# PD.net
KiCad netlist of a schematic drawn in EAGLE
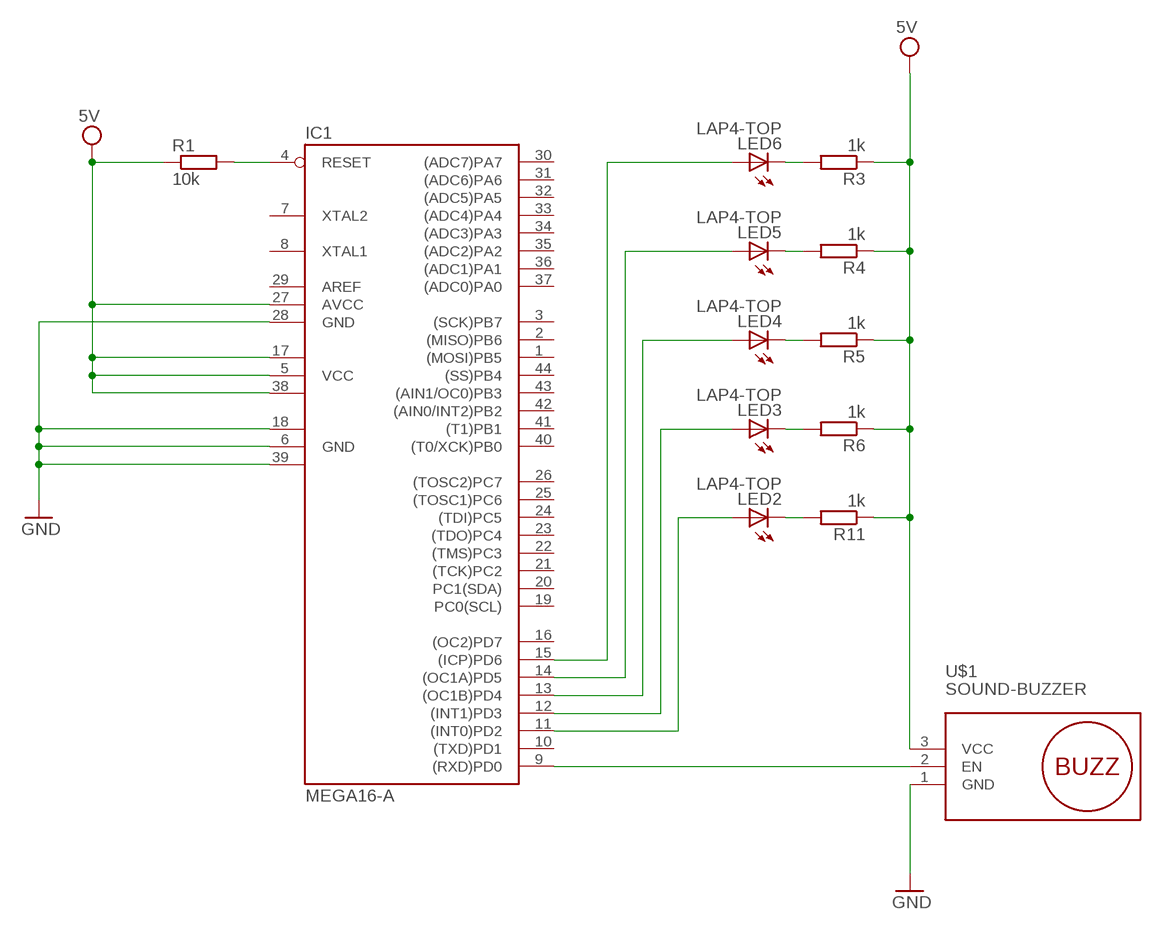
[diagram p0: schematic, sheet 1]

(export (version "E")
  (design (tool "Eeschema 10.0.6"))
  (components
    (comp (ref "IC1")
      (value "MEGA16-A")
      (footprint "eagle-import:TQFP44")
      (fields (field (name "MPN") "ATMEGA16-16AU"))
      (libsource (lib "eagle-import") (part "MEGA16-A"))
    )
    (comp (ref "LED2")
      (value "LAP4-TOP")
      (footprint "eagle-import:P47F-TOP")
      (libsource (lib "eagle-import") (part "P4-TOPLA"))
    )
    (comp (ref "LED3")
      (value "LAP4-TOP")
      (footprint "eagle-import:P47F-TOP")
      (libsource (lib "eagle-import") (part "P4-TOPLA"))
    )
    (comp (ref "LED4")
      (value "LAP4-TOP")
      (footprint "eagle-import:P47F-TOP")
      (libsource (lib "eagle-import") (part "P4-TOPLA"))
    )
    (comp (ref "LED5")
      (value "LAP4-TOP")
      (footprint "eagle-import:P47F-TOP")
      (libsource (lib "eagle-import") (part "P4-TOPLA"))
    )
    (comp (ref "LED6")
      (value "LAP4-TOP")
      (footprint "eagle-import:P47F-TOP")
      (libsource (lib "eagle-import") (part "P4-TOPLA"))
    )
    (comp (ref "R1")
      (value "10k")
      (footprint "eagle-import:M0805")
      (libsource (lib "eagle-import") (part "R-EU_M0805"))
    )
    (comp (ref "R3")
      (value "1k")
      (footprint "eagle-import:M0805")
      (libsource (lib "eagle-import") (part "R-EU_M0805"))
    )
    (comp (ref "R4")
      (value "1k")
      (footprint "eagle-import:M0805")
      (libsource (lib "eagle-import") (part "R-EU_M0805"))
    )
    (comp (ref "R5")
      (value "1k")
      (footprint "eagle-import:M0805")
      (libsource (lib "eagle-import") (part "R-EU_M0805"))
    )
    (comp (ref "R6")
      (value "1k")
      (footprint "eagle-import:M0805")
      (libsource (lib "eagle-import") (part "R-EU_M0805"))
    )
    (comp (ref "R11")
      (value "1k")
      (footprint "eagle-import:M0805")
      (libsource (lib "eagle-import") (part "R-EU_M0805"))
    )
    (comp (ref "U$1")
      (value "SOUND-BUZZER")
      (footprint "eagle-import:SOUND-BUZZER")
      (libsource (lib "eagle-import") (part "SOUND-BUZZER"))
    )
  )
  (nets
    (net (code "1") (name "5V") (class "Default")
      (node (ref "IC1") (pin "17") (pinfunction "VCC1_17") (pintype "power_in"))
      (node (ref "IC1") (pin "27") (pinfunction "AVCC_27") (pintype "power_in"))
      (node (ref "IC1") (pin "38") (pinfunction "VCC2_38") (pintype "power_in"))
      (node (ref "IC1") (pin "5") (pinfunction "VCC_5") (pintype "power_in"))
      (node (ref "R1") (pin "1") (pinfunction "1_1") (pintype "passive"))
      (node (ref "R11") (pin "1") (pinfunction "1_1") (pintype "passive"))
      (node (ref "R3") (pin "1") (pinfunction "1_1") (pintype "passive"))
      (node (ref "R4") (pin "1") (pinfunction "1_1") (pintype "passive"))
      (node (ref "R5") (pin "1") (pinfunction "1_1") (pintype "passive"))
      (node (ref "R6") (pin "1") (pinfunction "1_1") (pintype "passive"))
      (node (ref "U$1") (pin "3") (pinfunction "VCC_3") (pintype "power_in"))
    )
    (net (code "2") (name "GND") (class "Default")
      (node (ref "IC1") (pin "18") (pinfunction "GND1_18") (pintype "power_in"))
      (node (ref "IC1") (pin "28") (pinfunction "GND_28") (pintype "power_in"))
      (node (ref "IC1") (pin "39") (pinfunction "GND2_39") (pintype "power_in"))
      (node (ref "IC1") (pin "6") (pinfunction "GND_6") (pintype "power_in"))
      (node (ref "U$1") (pin "1") (pinfunction "GND_1") (pintype "power_in"))
    )
    (net (code "3") (name "Net-(IC1-(ICP)PD6)") (class "Default")
      (node (ref "IC1") (pin "15") (pinfunction "(ICP)PD6_15") (pintype "bidirectional"))
      (node (ref "LED6") (pin "A") (pinfunction "A_A") (pintype "passive"))
    )
    (net (code "4") (name "Net-(IC1-(INT0)PD2)") (class "Default")
      (node (ref "IC1") (pin "11") (pinfunction "(INT0)PD2_11") (pintype "bidirectional"))
      (node (ref "LED2") (pin "A") (pinfunction "A_A") (pintype "passive"))
    )
    (net (code "5") (name "Net-(IC1-(INT1)PD3)") (class "Default")
      (node (ref "IC1") (pin "12") (pinfunction "(INT1)PD3_12") (pintype "bidirectional"))
      (node (ref "LED3") (pin "A") (pinfunction "A_A") (pintype "passive"))
    )
    (net (code "6") (name "Net-(IC1-(OC1A)PD5)") (class "Default")
      (node (ref "IC1") (pin "14") (pinfunction "(OC1A)PD5_14") (pintype "bidirectional"))
      (node (ref "LED5") (pin "A") (pinfunction "A_A") (pintype "passive"))
    )
    (net (code "7") (name "Net-(IC1-(OC1B)PD4)") (class "Default")
      (node (ref "IC1") (pin "13") (pinfunction "(OC1B)PD4_13") (pintype "bidirectional"))
      (node (ref "LED4") (pin "A") (pinfunction "A_A") (pintype "passive"))
    )
    (net (code "8") (name "Net-(IC1-(RXD)PD0)") (class "Default")
      (node (ref "IC1") (pin "9") (pinfunction "(RXD)PD0_9") (pintype "bidirectional"))
      (node (ref "U$1") (pin "2") (pinfunction "EN_2") (pintype "input"))
    )
    (net (code "9") (name "Net-(IC1-RESET)") (class "Default")
      (node (ref "IC1") (pin "4") (pinfunction "RESET_4") (pintype "input"))
      (node (ref "R1") (pin "2") (pinfunction "2_2") (pintype "passive"))
    )
    (net (code "10") (name "Net-(LED2-PadC)") (class "Default")
      (node (ref "LED2") (pin "C") (pinfunction "C_C") (pintype "passive"))
      (node (ref "R11") (pin "2") (pinfunction "2_2") (pintype "passive"))
    )
    (net (code "11") (name "Net-(LED3-PadC)") (class "Default")
      (node (ref "LED3") (pin "C") (pinfunction "C_C") (pintype "passive"))
      (node (ref "R6") (pin "2") (pinfunction "2_2") (pintype "passive"))
    )
    (net (code "12") (name "Net-(LED4-PadC)") (class "Default")
      (node (ref "LED4") (pin "C") (pinfunction "C_C") (pintype "passive"))
      (node (ref "R5") (pin "2") (pinfunction "2_2") (pintype "passive"))
    )
    (net (code "13") (name "Net-(LED5-PadC)") (class "Default")
      (node (ref "LED5") (pin "C") (pinfunction "C_C") (pintype "passive"))
      (node (ref "R4") (pin "2") (pinfunction "2_2") (pintype "passive"))
    )
    (net (code "14") (name "Net-(LED6-PadC)") (class "Default")
      (node (ref "LED6") (pin "C") (pinfunction "C_C") (pintype "passive"))
      (node (ref "R3") (pin "2") (pinfunction "2_2") (pintype "passive"))
    )
    (net (code "15") (name "unconnected-(IC1-(ADC0)PA0-Pad37)") (class "Default")
      (node (ref "IC1") (pin "37") (pinfunction "(ADC0)PA0_37") (pintype "bidirectional"))
    )
    (net (code "16") (name "unconnected-(IC1-(ADC1)PA1-Pad36)") (class "Default")
      (node (ref "IC1") (pin "36") (pinfunction "(ADC1)PA1_36") (pintype "bidirectional"))
    )
    (net (code "17") (name "unconnected-(IC1-(ADC2)PA2-Pad35)") (class "Default")
      (node (ref "IC1") (pin "35") (pinfunction "(ADC2)PA2_35") (pintype "bidirectional"))
    )
    (net (code "18") (name "unconnected-(IC1-(ADC3)PA3-Pad34)") (class "Default")
      (node (ref "IC1") (pin "34") (pinfunction "(ADC3)PA3_34") (pintype "bidirectional"))
    )
    (net (code "19") (name "unconnected-(IC1-(ADC4)PA4-Pad33)") (class "Default")
      (node (ref "IC1") (pin "33") (pinfunction "(ADC4)PA4_33") (pintype "bidirectional"))
    )
    (net (code "20") (name "unconnected-(IC1-(ADC5)PA5-Pad32)") (class "Default")
      (node (ref "IC1") (pin "32") (pinfunction "(ADC5)PA5_32") (pintype "bidirectional"))
    )
    (net (code "21") (name "unconnected-(IC1-(ADC6)PA6-Pad31)") (class "Default")
      (node (ref "IC1") (pin "31") (pinfunction "(ADC6)PA6_31") (pintype "bidirectional"))
    )
    (net (code "22") (name "unconnected-(IC1-(ADC7)PA7-Pad30)") (class "Default")
      (node (ref "IC1") (pin "30") (pinfunction "(ADC7)PA7_30") (pintype "bidirectional"))
    )
    (net (code "23") (name "unconnected-(IC1-(AIN0{slash}INT2)PB2-Pad42)") (class "Default")
      (node (ref "IC1") (pin "42") (pinfunction "(AIN0/INT2)PB2_42") (pintype "bidirectional"))
    )
    (net (code "24") (name "unconnected-(IC1-(AIN1{slash}OC0)PB3-Pad43)") (class "Default")
      (node (ref "IC1") (pin "43") (pinfunction "(AIN1/OC0)PB3_43") (pintype "bidirectional"))
    )
    (net (code "25") (name "unconnected-(IC1-(MISO)PB6-Pad2)") (class "Default")
      (node (ref "IC1") (pin "2") (pinfunction "(MISO)PB6_2") (pintype "bidirectional"))
    )
    (net (code "26") (name "unconnected-(IC1-(MOSI)PB5-Pad1)") (class "Default")
      (node (ref "IC1") (pin "1") (pinfunction "(MOSI)PB5_1") (pintype "bidirectional"))
    )
    (net (code "27") (name "unconnected-(IC1-(OC2)PD7-Pad16)") (class "Default")
      (node (ref "IC1") (pin "16") (pinfunction "(OC2)PD7_16") (pintype "bidirectional"))
    )
    (net (code "28") (name "unconnected-(IC1-(SCK)PB7-Pad3)") (class "Default")
      (node (ref "IC1") (pin "3") (pinfunction "(SCK)PB7_3") (pintype "bidirectional"))
    )
    (net (code "29") (name "unconnected-(IC1-(SS)PB4-Pad44)") (class "Default")
      (node (ref "IC1") (pin "44") (pinfunction "(SS)PB4_44") (pintype "bidirectional"))
    )
    (net (code "30") (name "unconnected-(IC1-(T0{slash}XCK)PB0-Pad40)") (class "Default")
      (node (ref "IC1") (pin "40") (pinfunction "(T0/XCK)PB0_40") (pintype "bidirectional"))
    )
    (net (code "31") (name "unconnected-(IC1-(T1)PB1-Pad41)") (class "Default")
      (node (ref "IC1") (pin "41") (pinfunction "(T1)PB1_41") (pintype "bidirectional"))
    )
    (net (code "32") (name "unconnected-(IC1-(TCK)PC2-Pad21)") (class "Default")
      (node (ref "IC1") (pin "21") (pinfunction "(TCK)PC2_21") (pintype "bidirectional"))
    )
    (net (code "33") (name "unconnected-(IC1-(TDI)PC5-Pad24)") (class "Default")
      (node (ref "IC1") (pin "24") (pinfunction "(TDI)PC5_24") (pintype "bidirectional"))
    )
    (net (code "34") (name "unconnected-(IC1-(TDO)PC4-Pad23)") (class "Default")
      (node (ref "IC1") (pin "23") (pinfunction "(TDO)PC4_23") (pintype "bidirectional"))
    )
    (net (code "35") (name "unconnected-(IC1-(TMS)PC3-Pad22)") (class "Default")
      (node (ref "IC1") (pin "22") (pinfunction "(TMS)PC3_22") (pintype "bidirectional"))
    )
    (net (code "36") (name "unconnected-(IC1-(TOSC1)PC6-Pad25)") (class "Default")
      (node (ref "IC1") (pin "25") (pinfunction "(TOSC1)PC6_25") (pintype "bidirectional"))
    )
    (net (code "37") (name "unconnected-(IC1-(TOSC2)PC7-Pad26)") (class "Default")
      (node (ref "IC1") (pin "26") (pinfunction "(TOSC2)PC7_26") (pintype "bidirectional"))
    )
    (net (code "38") (name "unconnected-(IC1-(TXD)PD1-Pad10)") (class "Default")
      (node (ref "IC1") (pin "10") (pinfunction "(TXD)PD1_10") (pintype "bidirectional"))
    )
    (net (code "39") (name "unconnected-(IC1-AREF-Pad29)") (class "Default")
      (node (ref "IC1") (pin "29") (pinfunction "AREF_29") (pintype "passive"))
    )
    (net (code "40") (name "unconnected-(IC1-PC0(SCL)-Pad19)") (class "Default")
      (node (ref "IC1") (pin "19") (pinfunction "PC0(SCL)_19") (pintype "bidirectional"))
    )
    (net (code "41") (name "unconnected-(IC1-PC1(SDA)-Pad20)") (class "Default")
      (node (ref "IC1") (pin "20") (pinfunction "PC1(SDA)_20") (pintype "bidirectional"))
    )
    (net (code "42") (name "unconnected-(IC1-XTAL1-Pad8)") (class "Default")
      (node (ref "IC1") (pin "8") (pinfunction "XTAL1_8") (pintype "bidirectional"))
    )
    (net (code "43") (name "unconnected-(IC1-XTAL2-Pad7)") (class "Default")
      (node (ref "IC1") (pin "7") (pinfunction "XTAL2_7") (pintype "bidirectional"))
    )
  )
)
